# Mainboard_Motordriver_Interface.net
KiCad netlist of a schematic drawn in Altium Designer
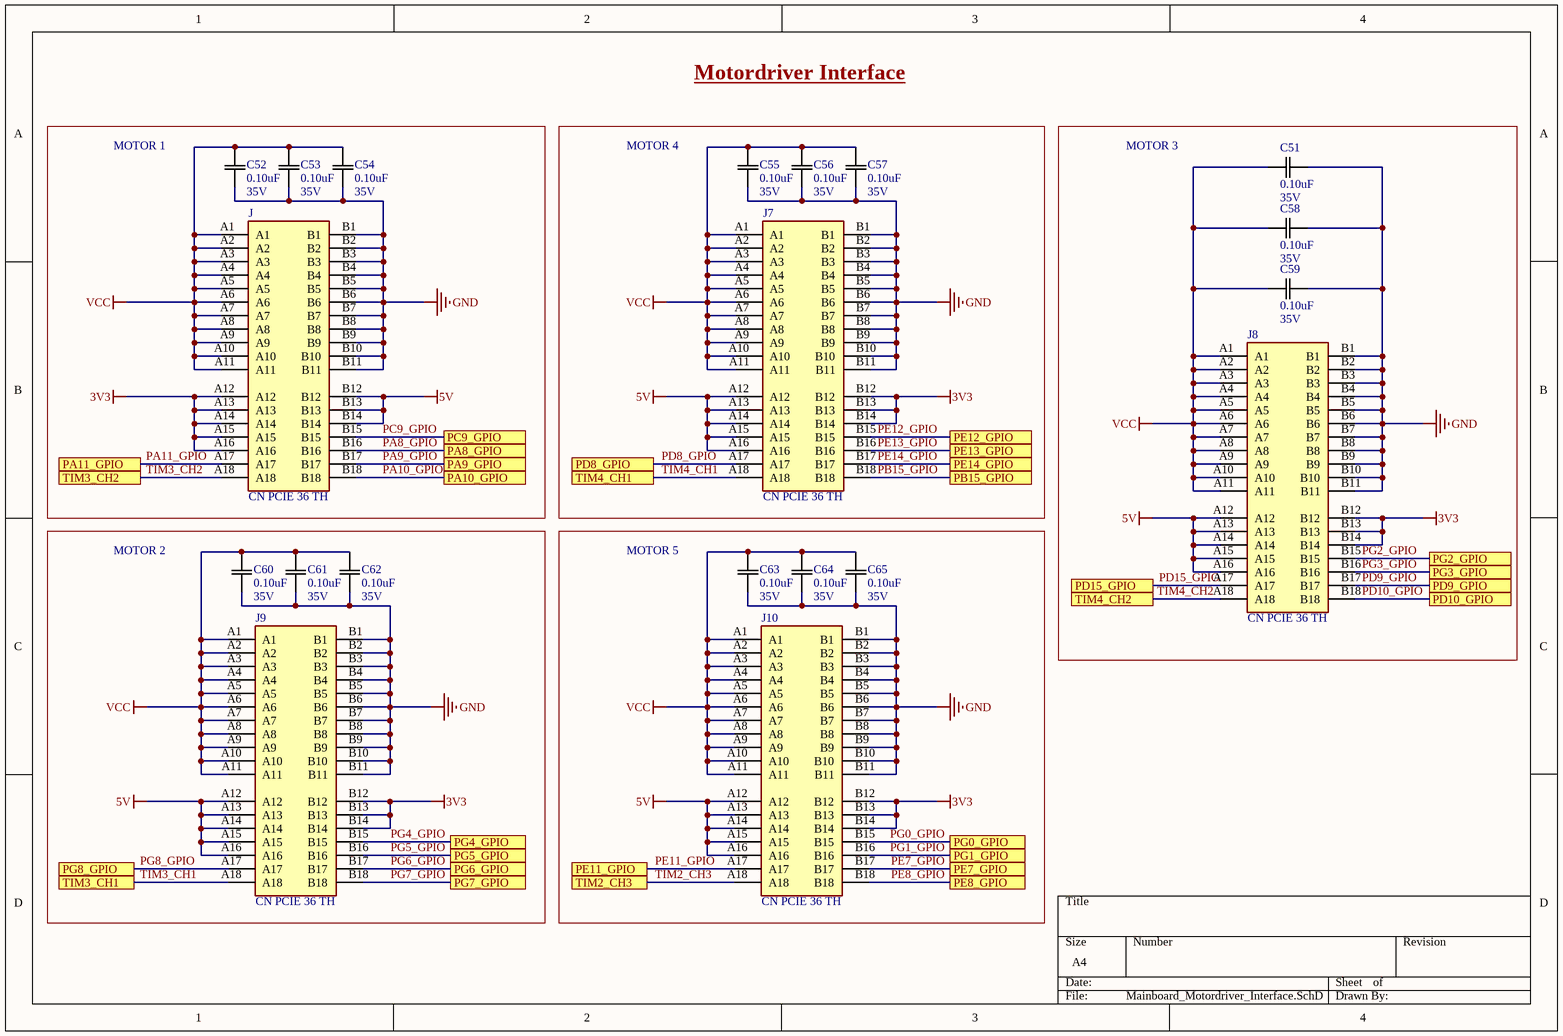
[diagram p0: Mainboard_Motordriver_Interface.SchDoc]

(export (version "E")
  (design (tool "Eeschema 10.0.6"))
  (components
    (comp (ref "C51")
      (value "0.10uF")
      (footprint "0603")
      (description "CAP CER 0.10UF 35V X7R 0603/0805")
      (fields (field (name "TOLERANCE") "10%") (field (name "RATING") "35V"))
      (libsource (lib "AltiumLibraries") (part "CAP 0.10uF 35V"))
    )
    (comp (ref "C52")
      (value "0.10uF")
      (footprint "0603")
      (description "CAP CER 0.10UF 35V X7R 0603/0805")
      (fields (field (name "TOLERANCE") "10%") (field (name "RATING") "35V"))
      (libsource (lib "AltiumLibraries") (part "CAP 0.10uF 35V"))
    )
    (comp (ref "C53")
      (value "0.10uF")
      (footprint "0603")
      (description "CAP CER 0.10UF 35V X7R 0603/0805")
      (fields (field (name "TOLERANCE") "10%") (field (name "RATING") "35V"))
      (libsource (lib "AltiumLibraries") (part "CAP 0.10uF 35V"))
    )
    (comp (ref "C54")
      (value "0.10uF")
      (footprint "0603")
      (description "CAP CER 0.10UF 35V X7R 0603/0805")
      (fields (field (name "TOLERANCE") "10%") (field (name "RATING") "35V"))
      (libsource (lib "AltiumLibraries") (part "CAP 0.10uF 35V"))
    )
    (comp (ref "C55")
      (value "0.10uF")
      (footprint "0603")
      (description "CAP CER 0.10UF 35V X7R 0603/0805")
      (fields (field (name "TOLERANCE") "10%") (field (name "RATING") "35V"))
      (libsource (lib "AltiumLibraries") (part "CAP 0.10uF 35V"))
    )
    (comp (ref "C56")
      (value "0.10uF")
      (footprint "0603")
      (description "CAP CER 0.10UF 35V X7R 0603/0805")
      (fields (field (name "TOLERANCE") "10%") (field (name "RATING") "35V"))
      (libsource (lib "AltiumLibraries") (part "CAP 0.10uF 35V"))
    )
    (comp (ref "C57")
      (value "0.10uF")
      (footprint "0603")
      (description "CAP CER 0.10UF 35V X7R 0603/0805")
      (fields (field (name "TOLERANCE") "10%") (field (name "RATING") "35V"))
      (libsource (lib "AltiumLibraries") (part "CAP 0.10uF 35V"))
    )
    (comp (ref "C58")
      (value "0.10uF")
      (footprint "0603")
      (description "CAP CER 0.10UF 35V X7R 0603/0805")
      (fields (field (name "TOLERANCE") "10%") (field (name "RATING") "35V"))
      (libsource (lib "AltiumLibraries") (part "CAP 0.10uF 35V"))
    )
    (comp (ref "C59")
      (value "0.10uF")
      (footprint "0603")
      (description "CAP CER 0.10UF 35V X7R 0603/0805")
      (fields (field (name "TOLERANCE") "10%") (field (name "RATING") "35V"))
      (libsource (lib "AltiumLibraries") (part "CAP 0.10uF 35V"))
    )
    (comp (ref "C60")
      (value "0.10uF")
      (footprint "0603")
      (description "CAP CER 0.10UF 35V X7R 0603/0805")
      (fields (field (name "TOLERANCE") "10%") (field (name "RATING") "35V"))
      (libsource (lib "AltiumLibraries") (part "CAP 0.10uF 35V"))
    )
    (comp (ref "C61")
      (value "0.10uF")
      (footprint "0603")
      (description "CAP CER 0.10UF 35V X7R 0603/0805")
      (fields (field (name "TOLERANCE") "10%") (field (name "RATING") "35V"))
      (libsource (lib "AltiumLibraries") (part "CAP 0.10uF 35V"))
    )
    (comp (ref "C62")
      (value "0.10uF")
      (footprint "0603")
      (description "CAP CER 0.10UF 35V X7R 0603/0805")
      (fields (field (name "TOLERANCE") "10%") (field (name "RATING") "35V"))
      (libsource (lib "AltiumLibraries") (part "CAP 0.10uF 35V"))
    )
    (comp (ref "C63")
      (value "0.10uF")
      (footprint "0603")
      (description "CAP CER 0.10UF 35V X7R 0603/0805")
      (fields (field (name "TOLERANCE") "10%") (field (name "RATING") "35V"))
      (libsource (lib "AltiumLibraries") (part "CAP 0.10uF 35V"))
    )
    (comp (ref "C64")
      (value "0.10uF")
      (footprint "0603")
      (description "CAP CER 0.10UF 35V X7R 0603/0805")
      (fields (field (name "TOLERANCE") "10%") (field (name "RATING") "35V"))
      (libsource (lib "AltiumLibraries") (part "CAP 0.10uF 35V"))
    )
    (comp (ref "C65")
      (value "0.10uF")
      (footprint "0603")
      (description "CAP CER 0.10UF 35V X7R 0603/0805")
      (fields (field (name "TOLERANCE") "10%") (field (name "RATING") "35V"))
      (libsource (lib "AltiumLibraries") (part "CAP 0.10uF 35V"))
    )
    (comp (ref "J")
      (value "CN PCIE 36 TH")
      (footprint "CN PCIE 36 TH")
      (description "36 Position Female Connector PCI Expressâ„¢ Gold 0.039 _1.00mm_ Black 10018784-10210TLF")
      (fields (field (name "MP") "10018784-10210TLF") (field (name "MF") "Amphenol ICC"))
      (libsource (lib "AltiumLibraries") (part "CN PCIE 36 TH"))
    )
    (comp (ref "J7")
      (value "CN PCIE 36 TH")
      (footprint "CN PCIE 36 TH")
      (description "36 Position Female Connector PCI Expressâ„¢ Gold 0.039 _1.00mm_ Black 10018784-10210TLF")
      (fields (field (name "MP") "10018784-10210TLF") (field (name "MF") "Amphenol ICC"))
      (libsource (lib "AltiumLibraries") (part "CN PCIE 36 TH"))
    )
    (comp (ref "J8")
      (value "CN PCIE 36 TH")
      (footprint "CN PCIE 36 TH")
      (description "36 Position Female Connector PCI Expressâ„¢ Gold 0.039 _1.00mm_ Black 10018784-10210TLF")
      (fields (field (name "MP") "10018784-10210TLF") (field (name "MF") "Amphenol ICC"))
      (libsource (lib "AltiumLibraries") (part "CN PCIE 36 TH"))
    )
    (comp (ref "J9")
      (value "CN PCIE 36 TH")
      (footprint "CN PCIE 36 TH")
      (description "36 Position Female Connector PCI Expressâ„¢ Gold 0.039 _1.00mm_ Black 10018784-10210TLF")
      (fields (field (name "MP") "10018784-10210TLF") (field (name "MF") "Amphenol ICC"))
      (libsource (lib "AltiumLibraries") (part "CN PCIE 36 TH"))
    )
    (comp (ref "J10")
      (value "CN PCIE 36 TH")
      (footprint "CN PCIE 36 TH")
      (description "36 Position Female Connector PCI Expressâ„¢ Gold 0.039 _1.00mm_ Black 10018784-10210TLF")
      (fields (field (name "MP") "10018784-10210TLF") (field (name "MF") "Amphenol ICC"))
      (libsource (lib "AltiumLibraries") (part "CN PCIE 36 TH"))
    )
  )
  (nets
    (net (code "1") (name "/PA8_GPIO") (class "Default")
      (node (ref "J") (pin "B16") (pinfunction "B16_B16") (pintype "passive"))
    )
    (net (code "2") (name "/PA9_GPIO") (class "Default")
      (node (ref "J") (pin "B17") (pinfunction "B17_B17") (pintype "passive"))
    )
    (net (code "3") (name "/PA10_GPIO") (class "Default")
      (node (ref "J") (pin "B18") (pinfunction "B18_B18") (pintype "passive"))
    )
    (net (code "4") (name "/PA11_GPIO") (class "Default")
      (node (ref "J") (pin "A17") (pinfunction "A17_A17") (pintype "passive"))
    )
    (net (code "5") (name "/PB15_GPIO") (class "Default")
      (node (ref "J7") (pin "B18") (pinfunction "B18_B18") (pintype "passive"))
    )
    (net (code "6") (name "/PC9_GPIO") (class "Default")
      (node (ref "J") (pin "B15") (pinfunction "B15_B15") (pintype "passive"))
    )
    (net (code "7") (name "/PD8_GPIO") (class "Default")
      (node (ref "J7") (pin "A17") (pinfunction "A17_A17") (pintype "passive"))
    )
    (net (code "8") (name "/PD9_GPIO") (class "Default")
      (node (ref "J8") (pin "B17") (pinfunction "B17_B17") (pintype "passive"))
    )
    (net (code "9") (name "/PD10_GPIO") (class "Default")
      (node (ref "J8") (pin "B18") (pinfunction "B18_B18") (pintype "passive"))
    )
    (net (code "10") (name "/PD15_GPIO") (class "Default")
      (node (ref "J8") (pin "A17") (pinfunction "A17_A17") (pintype "passive"))
    )
    (net (code "11") (name "/PE7_GPIO") (class "Default")
      (node (ref "J10") (pin "B17") (pinfunction "B17_B17") (pintype "passive"))
    )
    (net (code "12") (name "/PE8_GPIO") (class "Default")
      (node (ref "J10") (pin "B18") (pinfunction "B18_B18") (pintype "passive"))
    )
    (net (code "13") (name "/PE11_GPIO") (class "Default")
      (node (ref "J10") (pin "A17") (pinfunction "A17_A17") (pintype "passive"))
    )
    (net (code "14") (name "/PE12_GPIO") (class "Default")
      (node (ref "J7") (pin "B15") (pinfunction "B15_B15") (pintype "passive"))
    )
    (net (code "15") (name "/PE13_GPIO") (class "Default")
      (node (ref "J7") (pin "B16") (pinfunction "B16_B16") (pintype "passive"))
    )
    (net (code "16") (name "/PE14_GPIO") (class "Default")
      (node (ref "J7") (pin "B17") (pinfunction "B17_B17") (pintype "passive"))
    )
    (net (code "17") (name "/PG0_GPIO") (class "Default")
      (node (ref "J10") (pin "B15") (pinfunction "B15_B15") (pintype "passive"))
    )
    (net (code "18") (name "/PG1_GPIO") (class "Default")
      (node (ref "J10") (pin "B16") (pinfunction "B16_B16") (pintype "passive"))
    )
    (net (code "19") (name "/PG2_GPIO") (class "Default")
      (node (ref "J8") (pin "B15") (pinfunction "B15_B15") (pintype "passive"))
    )
    (net (code "20") (name "/PG3_GPIO") (class "Default")
      (node (ref "J8") (pin "B16") (pinfunction "B16_B16") (pintype "passive"))
    )
    (net (code "21") (name "/PG4_GPIO") (class "Default")
      (node (ref "J9") (pin "B15") (pinfunction "B15_B15") (pintype "passive"))
    )
    (net (code "22") (name "/PG5_GPIO") (class "Default")
      (node (ref "J9") (pin "B16") (pinfunction "B16_B16") (pintype "passive"))
    )
    (net (code "23") (name "/PG6_GPIO") (class "Default")
      (node (ref "J9") (pin "B17") (pinfunction "B17_B17") (pintype "passive"))
    )
    (net (code "24") (name "/PG7_GPIO") (class "Default")
      (node (ref "J9") (pin "B18") (pinfunction "B18_B18") (pintype "passive"))
    )
    (net (code "25") (name "/PG8_GPIO") (class "Default")
      (node (ref "J9") (pin "A17") (pinfunction "A17_A17") (pintype "passive"))
    )
    (net (code "26") (name "/TIM2_CH3") (class "Default")
      (node (ref "J10") (pin "A18") (pinfunction "A18_A18") (pintype "passive"))
    )
    (net (code "27") (name "/TIM3_CH1") (class "Default")
      (node (ref "J9") (pin "A18") (pinfunction "A18_A18") (pintype "passive"))
    )
    (net (code "28") (name "/TIM3_CH2") (class "Default")
      (node (ref "J") (pin "A18") (pinfunction "A18_A18") (pintype "passive"))
    )
    (net (code "29") (name "/TIM4_CH1") (class "Default")
      (node (ref "J7") (pin "A18") (pinfunction "A18_A18") (pintype "passive"))
    )
    (net (code "30") (name "/TIM4_CH2") (class "Default")
      (node (ref "J8") (pin "A18") (pinfunction "A18_A18") (pintype "passive"))
    )
    (net (code "31") (name "3V3") (class "Default")
      (node (ref "J") (pin "A12") (pinfunction "A12_A12") (pintype "passive"))
      (node (ref "J") (pin "A13") (pinfunction "A13_A13") (pintype "passive"))
      (node (ref "J") (pin "A14") (pinfunction "A14_A14") (pintype "passive"))
      (node (ref "J") (pin "A15") (pinfunction "A15_A15") (pintype "passive"))
      (node (ref "J") (pin "A16") (pinfunction "A16_A16") (pintype "passive"))
      (node (ref "J10") (pin "B12") (pinfunction "B12_B12") (pintype "passive"))
      (node (ref "J10") (pin "B13") (pinfunction "B13_B13") (pintype "passive"))
      (node (ref "J10") (pin "B14") (pinfunction "B14_B14") (pintype "passive"))
      (node (ref "J7") (pin "B12") (pinfunction "B12_B12") (pintype "passive"))
      (node (ref "J7") (pin "B13") (pinfunction "B13_B13") (pintype "passive"))
      (node (ref "J7") (pin "B14") (pinfunction "B14_B14") (pintype "passive"))
      (node (ref "J8") (pin "B12") (pinfunction "B12_B12") (pintype "passive"))
      (node (ref "J8") (pin "B13") (pinfunction "B13_B13") (pintype "passive"))
      (node (ref "J8") (pin "B14") (pinfunction "B14_B14") (pintype "passive"))
      (node (ref "J9") (pin "B12") (pinfunction "B12_B12") (pintype "passive"))
      (node (ref "J9") (pin "B13") (pinfunction "B13_B13") (pintype "passive"))
      (node (ref "J9") (pin "B14") (pinfunction "B14_B14") (pintype "passive"))
    )
    (net (code "32") (name "5V") (class "Default")
      (node (ref "J") (pin "B12") (pinfunction "B12_B12") (pintype "passive"))
      (node (ref "J") (pin "B13") (pinfunction "B13_B13") (pintype "passive"))
      (node (ref "J") (pin "B14") (pinfunction "B14_B14") (pintype "passive"))
      (node (ref "J10") (pin "A12") (pinfunction "A12_A12") (pintype "passive"))
      (node (ref "J10") (pin "A13") (pinfunction "A13_A13") (pintype "passive"))
      (node (ref "J10") (pin "A14") (pinfunction "A14_A14") (pintype "passive"))
      (node (ref "J10") (pin "A15") (pinfunction "A15_A15") (pintype "passive"))
      (node (ref "J10") (pin "A16") (pinfunction "A16_A16") (pintype "passive"))
      (node (ref "J7") (pin "A12") (pinfunction "A12_A12") (pintype "passive"))
      (node (ref "J7") (pin "A13") (pinfunction "A13_A13") (pintype "passive"))
      (node (ref "J7") (pin "A14") (pinfunction "A14_A14") (pintype "passive"))
      (node (ref "J7") (pin "A15") (pinfunction "A15_A15") (pintype "passive"))
      (node (ref "J7") (pin "A16") (pinfunction "A16_A16") (pintype "passive"))
      (node (ref "J8") (pin "A12") (pinfunction "A12_A12") (pintype "passive"))
      (node (ref "J8") (pin "A13") (pinfunction "A13_A13") (pintype "passive"))
      (node (ref "J8") (pin "A14") (pinfunction "A14_A14") (pintype "passive"))
      (node (ref "J8") (pin "A15") (pinfunction "A15_A15") (pintype "passive"))
      (node (ref "J8") (pin "A16") (pinfunction "A16_A16") (pintype "passive"))
      (node (ref "J9") (pin "A12") (pinfunction "A12_A12") (pintype "passive"))
      (node (ref "J9") (pin "A13") (pinfunction "A13_A13") (pintype "passive"))
      (node (ref "J9") (pin "A14") (pinfunction "A14_A14") (pintype "passive"))
      (node (ref "J9") (pin "A15") (pinfunction "A15_A15") (pintype "passive"))
      (node (ref "J9") (pin "A16") (pinfunction "A16_A16") (pintype "passive"))
    )
    (net (code "33") (name "GND") (class "Default")
      (node (ref "C51") (pin "1") (pinfunction "C1_1") (pintype "passive"))
      (node (ref "C52") (pin "1") (pinfunction "C1_1") (pintype "passive"))
      (node (ref "C53") (pin "1") (pinfunction "C1_1") (pintype "passive"))
      (node (ref "C54") (pin "1") (pinfunction "C1_1") (pintype "passive"))
      (node (ref "C55") (pin "1") (pinfunction "C1_1") (pintype "passive"))
      (node (ref "C56") (pin "1") (pinfunction "C1_1") (pintype "passive"))
      (node (ref "C57") (pin "1") (pinfunction "C1_1") (pintype "passive"))
      (node (ref "C58") (pin "1") (pinfunction "C1_1") (pintype "passive"))
      (node (ref "C59") (pin "1") (pinfunction "C1_1") (pintype "passive"))
      (node (ref "C60") (pin "1") (pinfunction "C1_1") (pintype "passive"))
      (node (ref "C61") (pin "1") (pinfunction "C1_1") (pintype "passive"))
      (node (ref "C62") (pin "1") (pinfunction "C1_1") (pintype "passive"))
      (node (ref "C63") (pin "1") (pinfunction "C1_1") (pintype "passive"))
      (node (ref "C64") (pin "1") (pinfunction "C1_1") (pintype "passive"))
      (node (ref "C65") (pin "1") (pinfunction "C1_1") (pintype "passive"))
      (node (ref "J") (pin "B1") (pinfunction "B1_B1") (pintype "passive"))
      (node (ref "J") (pin "B10") (pinfunction "B10_B10") (pintype "passive"))
      (node (ref "J") (pin "B11") (pinfunction "B11_B11") (pintype "passive"))
      (node (ref "J") (pin "B2") (pinfunction "B2_B2") (pintype "passive"))
      (node (ref "J") (pin "B3") (pinfunction "B3_B3") (pintype "passive"))
      (node (ref "J") (pin "B4") (pinfunction "B4_B4") (pintype "passive"))
      (node (ref "J") (pin "B5") (pinfunction "B5_B5") (pintype "passive"))
      (node (ref "J") (pin "B6") (pinfunction "B6_B6") (pintype "passive"))
      (node (ref "J") (pin "B7") (pinfunction "B7_B7") (pintype "passive"))
      (node (ref "J") (pin "B8") (pinfunction "B8_B8") (pintype "passive"))
      (node (ref "J") (pin "B9") (pinfunction "B9_B9") (pintype "passive"))
      (node (ref "J10") (pin "B1") (pinfunction "B1_B1") (pintype "passive"))
      (node (ref "J10") (pin "B10") (pinfunction "B10_B10") (pintype "passive"))
      (node (ref "J10") (pin "B11") (pinfunction "B11_B11") (pintype "passive"))
      (node (ref "J10") (pin "B2") (pinfunction "B2_B2") (pintype "passive"))
      (node (ref "J10") (pin "B3") (pinfunction "B3_B3") (pintype "passive"))
      (node (ref "J10") (pin "B4") (pinfunction "B4_B4") (pintype "passive"))
      (node (ref "J10") (pin "B5") (pinfunction "B5_B5") (pintype "passive"))
      (node (ref "J10") (pin "B6") (pinfunction "B6_B6") (pintype "passive"))
      (node (ref "J10") (pin "B7") (pinfunction "B7_B7") (pintype "passive"))
      (node (ref "J10") (pin "B8") (pinfunction "B8_B8") (pintype "passive"))
      (node (ref "J10") (pin "B9") (pinfunction "B9_B9") (pintype "passive"))
      (node (ref "J7") (pin "B1") (pinfunction "B1_B1") (pintype "passive"))
      (node (ref "J7") (pin "B10") (pinfunction "B10_B10") (pintype "passive"))
      (node (ref "J7") (pin "B11") (pinfunction "B11_B11") (pintype "passive"))
      (node (ref "J7") (pin "B2") (pinfunction "B2_B2") (pintype "passive"))
      (node (ref "J7") (pin "B3") (pinfunction "B3_B3") (pintype "passive"))
      (node (ref "J7") (pin "B4") (pinfunction "B4_B4") (pintype "passive"))
      (node (ref "J7") (pin "B5") (pinfunction "B5_B5") (pintype "passive"))
      (node (ref "J7") (pin "B6") (pinfunction "B6_B6") (pintype "passive"))
      (node (ref "J7") (pin "B7") (pinfunction "B7_B7") (pintype "passive"))
      (node (ref "J7") (pin "B8") (pinfunction "B8_B8") (pintype "passive"))
      (node (ref "J7") (pin "B9") (pinfunction "B9_B9") (pintype "passive"))
      (node (ref "J8") (pin "B1") (pinfunction "B1_B1") (pintype "passive"))
      (node (ref "J8") (pin "B10") (pinfunction "B10_B10") (pintype "passive"))
      (node (ref "J8") (pin "B11") (pinfunction "B11_B11") (pintype "passive"))
      (node (ref "J8") (pin "B2") (pinfunction "B2_B2") (pintype "passive"))
      (node (ref "J8") (pin "B3") (pinfunction "B3_B3") (pintype "passive"))
      (node (ref "J8") (pin "B4") (pinfunction "B4_B4") (pintype "passive"))
      (node (ref "J8") (pin "B5") (pinfunction "B5_B5") (pintype "passive"))
      (node (ref "J8") (pin "B6") (pinfunction "B6_B6") (pintype "passive"))
      (node (ref "J8") (pin "B7") (pinfunction "B7_B7") (pintype "passive"))
      (node (ref "J8") (pin "B8") (pinfunction "B8_B8") (pintype "passive"))
      (node (ref "J8") (pin "B9") (pinfunction "B9_B9") (pintype "passive"))
      (node (ref "J9") (pin "B1") (pinfunction "B1_B1") (pintype "passive"))
      (node (ref "J9") (pin "B10") (pinfunction "B10_B10") (pintype "passive"))
      (node (ref "J9") (pin "B11") (pinfunction "B11_B11") (pintype "passive"))
      (node (ref "J9") (pin "B2") (pinfunction "B2_B2") (pintype "passive"))
      (node (ref "J9") (pin "B3") (pinfunction "B3_B3") (pintype "passive"))
      (node (ref "J9") (pin "B4") (pinfunction "B4_B4") (pintype "passive"))
      (node (ref "J9") (pin "B5") (pinfunction "B5_B5") (pintype "passive"))
      (node (ref "J9") (pin "B6") (pinfunction "B6_B6") (pintype "passive"))
      (node (ref "J9") (pin "B7") (pinfunction "B7_B7") (pintype "passive"))
      (node (ref "J9") (pin "B8") (pinfunction "B8_B8") (pintype "passive"))
      (node (ref "J9") (pin "B9") (pinfunction "B9_B9") (pintype "passive"))
    )
    (net (code "34") (name "VCC") (class "Default")
      (node (ref "C51") (pin "2") (pinfunction "C2_2") (pintype "passive"))
      (node (ref "C52") (pin "2") (pinfunction "C2_2") (pintype "passive"))
      (node (ref "C53") (pin "2") (pinfunction "C2_2") (pintype "passive"))
      (node (ref "C54") (pin "2") (pinfunction "C2_2") (pintype "passive"))
      (node (ref "C55") (pin "2") (pinfunction "C2_2") (pintype "passive"))
      (node (ref "C56") (pin "2") (pinfunction "C2_2") (pintype "passive"))
      (node (ref "C57") (pin "2") (pinfunction "C2_2") (pintype "passive"))
      (node (ref "C58") (pin "2") (pinfunction "C2_2") (pintype "passive"))
      (node (ref "C59") (pin "2") (pinfunction "C2_2") (pintype "passive"))
      (node (ref "C60") (pin "2") (pinfunction "C2_2") (pintype "passive"))
      (node (ref "C61") (pin "2") (pinfunction "C2_2") (pintype "passive"))
      (node (ref "C62") (pin "2") (pinfunction "C2_2") (pintype "passive"))
      (node (ref "C63") (pin "2") (pinfunction "C2_2") (pintype "passive"))
      (node (ref "C64") (pin "2") (pinfunction "C2_2") (pintype "passive"))
      (node (ref "C65") (pin "2") (pinfunction "C2_2") (pintype "passive"))
      (node (ref "J") (pin "A1") (pinfunction "A1_A1") (pintype "passive"))
      (node (ref "J") (pin "A10") (pinfunction "A10_A10") (pintype "passive"))
      (node (ref "J") (pin "A11") (pinfunction "A11_A11") (pintype "passive"))
      (node (ref "J") (pin "A2") (pinfunction "A2_A2") (pintype "passive"))
      (node (ref "J") (pin "A3") (pinfunction "A3_A3") (pintype "passive"))
      (node (ref "J") (pin "A4") (pinfunction "A4_A4") (pintype "passive"))
      (node (ref "J") (pin "A5") (pinfunction "A5_A5") (pintype "passive"))
      (node (ref "J") (pin "A6") (pinfunction "A6_A6") (pintype "passive"))
      (node (ref "J") (pin "A7") (pinfunction "A7_A7") (pintype "passive"))
      (node (ref "J") (pin "A8") (pinfunction "A8_A8") (pintype "passive"))
      (node (ref "J") (pin "A9") (pinfunction "A9_A9") (pintype "passive"))
      (node (ref "J10") (pin "A1") (pinfunction "A1_A1") (pintype "passive"))
      (node (ref "J10") (pin "A10") (pinfunction "A10_A10") (pintype "passive"))
      (node (ref "J10") (pin "A11") (pinfunction "A11_A11") (pintype "passive"))
      (node (ref "J10") (pin "A2") (pinfunction "A2_A2") (pintype "passive"))
      (node (ref "J10") (pin "A3") (pinfunction "A3_A3") (pintype "passive"))
      (node (ref "J10") (pin "A4") (pinfunction "A4_A4") (pintype "passive"))
      (node (ref "J10") (pin "A5") (pinfunction "A5_A5") (pintype "passive"))
      (node (ref "J10") (pin "A6") (pinfunction "A6_A6") (pintype "passive"))
      (node (ref "J10") (pin "A7") (pinfunction "A7_A7") (pintype "passive"))
      (node (ref "J10") (pin "A8") (pinfunction "A8_A8") (pintype "passive"))
      (node (ref "J10") (pin "A9") (pinfunction "A9_A9") (pintype "passive"))
      (node (ref "J7") (pin "A1") (pinfunction "A1_A1") (pintype "passive"))
      (node (ref "J7") (pin "A10") (pinfunction "A10_A10") (pintype "passive"))
      (node (ref "J7") (pin "A11") (pinfunction "A11_A11") (pintype "passive"))
      (node (ref "J7") (pin "A2") (pinfunction "A2_A2") (pintype "passive"))
      (node (ref "J7") (pin "A3") (pinfunction "A3_A3") (pintype "passive"))
      (node (ref "J7") (pin "A4") (pinfunction "A4_A4") (pintype "passive"))
      (node (ref "J7") (pin "A5") (pinfunction "A5_A5") (pintype "passive"))
      (node (ref "J7") (pin "A6") (pinfunction "A6_A6") (pintype "passive"))
      (node (ref "J7") (pin "A7") (pinfunction "A7_A7") (pintype "passive"))
      (node (ref "J7") (pin "A8") (pinfunction "A8_A8") (pintype "passive"))
      (node (ref "J7") (pin "A9") (pinfunction "A9_A9") (pintype "passive"))
      (node (ref "J8") (pin "A1") (pinfunction "A1_A1") (pintype "passive"))
      (node (ref "J8") (pin "A10") (pinfunction "A10_A10") (pintype "passive"))
      (node (ref "J8") (pin "A11") (pinfunction "A11_A11") (pintype "passive"))
      (node (ref "J8") (pin "A2") (pinfunction "A2_A2") (pintype "passive"))
      (node (ref "J8") (pin "A3") (pinfunction "A3_A3") (pintype "passive"))
      (node (ref "J8") (pin "A4") (pinfunction "A4_A4") (pintype "passive"))
      (node (ref "J8") (pin "A5") (pinfunction "A5_A5") (pintype "passive"))
      (node (ref "J8") (pin "A6") (pinfunction "A6_A6") (pintype "passive"))
      (node (ref "J8") (pin "A7") (pinfunction "A7_A7") (pintype "passive"))
      (node (ref "J8") (pin "A8") (pinfunction "A8_A8") (pintype "passive"))
      (node (ref "J8") (pin "A9") (pinfunction "A9_A9") (pintype "passive"))
      (node (ref "J9") (pin "A1") (pinfunction "A1_A1") (pintype "passive"))
      (node (ref "J9") (pin "A10") (pinfunction "A10_A10") (pintype "passive"))
      (node (ref "J9") (pin "A11") (pinfunction "A11_A11") (pintype "passive"))
      (node (ref "J9") (pin "A2") (pinfunction "A2_A2") (pintype "passive"))
      (node (ref "J9") (pin "A3") (pinfunction "A3_A3") (pintype "passive"))
      (node (ref "J9") (pin "A4") (pinfunction "A4_A4") (pintype "passive"))
      (node (ref "J9") (pin "A5") (pinfunction "A5_A5") (pintype "passive"))
      (node (ref "J9") (pin "A6") (pinfunction "A6_A6") (pintype "passive"))
      (node (ref "J9") (pin "A7") (pinfunction "A7_A7") (pintype "passive"))
      (node (ref "J9") (pin "A8") (pinfunction "A8_A8") (pintype "passive"))
      (node (ref "J9") (pin "A9") (pinfunction "A9_A9") (pintype "passive"))
    )
  )
)
